# BMS_AFE_-_Communications.net
KiCad netlist of a schematic drawn in Altium Designer
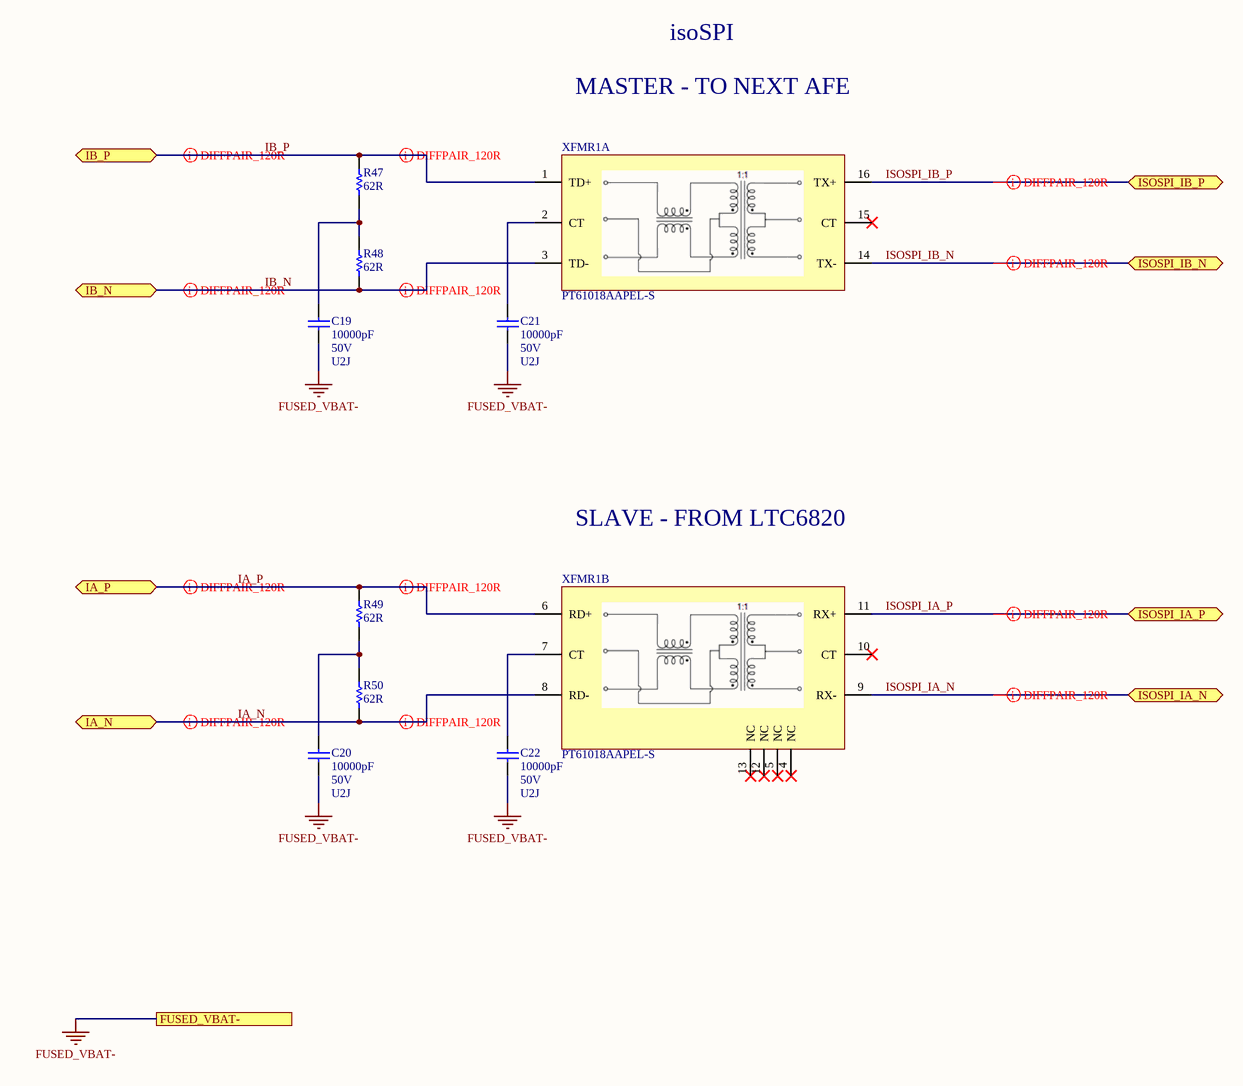
[diagram p0: BMS AFE - Communications.SchDoc]

(export (version "E")
  (design (tool "Eeschema 10.0.6"))
  (components
    (comp (ref "C19")
      (value "CAP CER 10nF 50V 5% X7R 0603")
      (footprint "CAP, 0603")
      (description "10000pF ±5% 50V Ceramic Capacitor U2J 0603 (1608 Metric)")
      (fields
        (field (name "TOLERANCE") "±5%")
        (field (name "CAPACITANCE") "10000pF")
        (field (name "VOLTAGE") "50V")
        (field (name "TEMPERATURE COEFFICIENT") "U2J")
      )
      (libsource (lib "Schematic Diagrams") (part "CAP CER 10nF 50V 5% X7R 0603"))
    )
    (comp (ref "C20")
      (value "CAP CER 10nF 50V 5% X7R 0603")
      (footprint "CAP, 0603")
      (description "10000pF ±5% 50V Ceramic Capacitor U2J 0603 (1608 Metric)")
      (fields
        (field (name "TOLERANCE") "±5%")
        (field (name "CAPACITANCE") "10000pF")
        (field (name "VOLTAGE") "50V")
        (field (name "TEMPERATURE COEFFICIENT") "U2J")
      )
      (libsource (lib "Schematic Diagrams") (part "CAP CER 10nF 50V 5% X7R 0603"))
    )
    (comp (ref "C21")
      (value "CAP CER 10nF 50V 5% X7R 0603")
      (footprint "CAP, 0603")
      (description "10000pF ±5% 50V Ceramic Capacitor U2J 0603 (1608 Metric)")
      (fields
        (field (name "TOLERANCE") "±5%")
        (field (name "CAPACITANCE") "10000pF")
        (field (name "VOLTAGE") "50V")
        (field (name "TEMPERATURE COEFFICIENT") "U2J")
      )
      (libsource (lib "Schematic Diagrams") (part "CAP CER 10nF 50V 5% X7R 0603"))
    )
    (comp (ref "C22")
      (value "CAP CER 10nF 50V 5% X7R 0603")
      (footprint "CAP, 0603")
      (description "10000pF ±5% 50V Ceramic Capacitor U2J 0603 (1608 Metric)")
      (fields
        (field (name "TOLERANCE") "±5%")
        (field (name "CAPACITANCE") "10000pF")
        (field (name "VOLTAGE") "50V")
        (field (name "TEMPERATURE COEFFICIENT") "U2J")
      )
      (libsource (lib "Schematic Diagrams") (part "CAP CER 10nF 50V 5% X7R 0603"))
    )
    (comp (ref "R47")
      (value "62R")
      (footprint "RES, 0603")
      (description "62 Ohms ±0.1% 0.1W, 1/10W Chip Resistor 0603 (1608 Metric) Automotive AEC-Q200 Thin Film")
      (fields
        (field (name "MANUFACTURER") "Panasonic Electronic Components")
        (field (name "MANUFACTURER PART NUMBER") "ERA-3AEB620V")
      )
      (libsource (lib "Schematic Diagrams") (part "RES 62 OHM 0.1% 1/10W 0603"))
    )
    (comp (ref "R48")
      (value "62R")
      (footprint "RES, 0603")
      (description "62 Ohms ±0.1% 0.1W, 1/10W Chip Resistor 0603 (1608 Metric) Automotive AEC-Q200 Thin Film")
      (fields
        (field (name "MANUFACTURER") "Panasonic Electronic Components")
        (field (name "MANUFACTURER PART NUMBER") "ERA-3AEB620V")
      )
      (libsource (lib "Schematic Diagrams") (part "RES 62 OHM 0.1% 1/10W 0603"))
    )
    (comp (ref "R49")
      (value "62R")
      (footprint "RES, 0603")
      (description "62 Ohms ±0.1% 0.1W, 1/10W Chip Resistor 0603 (1608 Metric) Automotive AEC-Q200 Thin Film")
      (fields
        (field (name "MANUFACTURER") "Panasonic Electronic Components")
        (field (name "MANUFACTURER PART NUMBER") "ERA-3AEB620V")
      )
      (libsource (lib "Schematic Diagrams") (part "RES 62 OHM 0.1% 1/10W 0603"))
    )
    (comp (ref "R50")
      (value "62R")
      (footprint "RES, 0603")
      (description "62 Ohms ±0.1% 0.1W, 1/10W Chip Resistor 0603 (1608 Metric) Automotive AEC-Q200 Thin Film")
      (fields
        (field (name "MANUFACTURER") "Panasonic Electronic Components")
        (field (name "MANUFACTURER PART NUMBER") "ERA-3AEB620V")
      )
      (libsource (lib "Schematic Diagrams") (part "RES 62 OHM 0.1% 1/10W 0603"))
    )
    (comp (ref "XFMR1")
      (value "IC PULSE XFMR 1CT:1CT 350UH SMD")
      (footprint "IC, PULSE XFMR 1CT:1CT 350UH SMD")
      (description "PULSE XFMR 1CT:1CT 350UH SMD")
      (fields (field (name "MANUFACTURER") "Bourns Inc.") (field (name "MFG_PN") "PT61018AAPEL-S"))
      (libsource (lib "Schematic Diagrams") (part "IC PULSE XFMR 1CT{colon}1CT 350UH SMD"))
    )
  )
  (nets
    (net (code "1") (name "/IA_N") (class "Default")
      (node (ref "R50") (pin "2") (pinfunction "2_2") (pintype "passive"))
      (node (ref "XFMR1") (pin "8") (pinfunction "RD-_8") (pintype "passive"))
    )
    (net (code "2") (name "/IA_P") (class "Default")
      (node (ref "R49") (pin "1") (pinfunction "1_1") (pintype "passive"))
      (node (ref "XFMR1") (pin "6") (pinfunction "RD+_6") (pintype "passive"))
    )
    (net (code "3") (name "/IB_N") (class "Default")
      (node (ref "R48") (pin "2") (pinfunction "2_2") (pintype "passive"))
      (node (ref "XFMR1") (pin "3") (pinfunction "TD-_3") (pintype "passive"))
    )
    (net (code "4") (name "/IB_P") (class "Default")
      (node (ref "R47") (pin "1") (pinfunction "1_1") (pintype "passive"))
      (node (ref "XFMR1") (pin "1") (pinfunction "TD+_1") (pintype "passive"))
    )
    (net (code "5") (name "/ISOSPI_IA_N") (class "Default")
      (node (ref "XFMR1") (pin "9") (pinfunction "RX-_9") (pintype "passive"))
    )
    (net (code "6") (name "/ISOSPI_IA_P") (class "Default")
      (node (ref "XFMR1") (pin "11") (pinfunction "RX+_11") (pintype "passive"))
    )
    (net (code "7") (name "/ISOSPI_IB_N") (class "Default")
      (node (ref "XFMR1") (pin "14") (pinfunction "TX-_14") (pintype "passive"))
    )
    (net (code "8") (name "/ISOSPI_IB_P") (class "Default")
      (node (ref "XFMR1") (pin "16") (pinfunction "TX+_16") (pintype "passive"))
    )
    (net (code "9") (name "FUSED_VBAT-") (class "Default")
      (node (ref "C19") (pin "2") (pinfunction "2_2") (pintype "passive"))
      (node (ref "C20") (pin "2") (pinfunction "2_2") (pintype "passive"))
      (node (ref "C21") (pin "2") (pinfunction "2_2") (pintype "passive"))
      (node (ref "C22") (pin "2") (pinfunction "2_2") (pintype "passive"))
    )
    (net (code "10") (name "Net-(C19-Pad1)") (class "Default")
      (node (ref "C19") (pin "1") (pinfunction "1_1") (pintype "passive"))
      (node (ref "R47") (pin "2") (pinfunction "2_2") (pintype "passive"))
      (node (ref "R48") (pin "1") (pinfunction "1_1") (pintype "passive"))
    )
    (net (code "11") (name "Net-(C20-Pad1)") (class "Default")
      (node (ref "C20") (pin "1") (pinfunction "1_1") (pintype "passive"))
      (node (ref "R49") (pin "2") (pinfunction "2_2") (pintype "passive"))
      (node (ref "R50") (pin "1") (pinfunction "1_1") (pintype "passive"))
    )
    (net (code "12") (name "Net-(C21-Pad1)") (class "Default")
      (node (ref "C21") (pin "1") (pinfunction "1_1") (pintype "passive"))
      (node (ref "XFMR1") (pin "2") (pinfunction "CT_2") (pintype "passive"))
    )
    (net (code "13") (name "Net-(C22-Pad1)") (class "Default")
      (node (ref "C22") (pin "1") (pinfunction "1_1") (pintype "passive"))
      (node (ref "XFMR1") (pin "7") (pinfunction "CT_7") (pintype "passive"))
    )
    (net (code "14") (name "unconnected-(XFMR1A-CT-Pad15)") (class "Default")
      (node (ref "XFMR1") (pin "15") (pinfunction "CT_15") (pintype "passive+no_connect"))
    )
    (net (code "15") (name "unconnected-(XFMR1B-CT-Pad10)") (class "Default")
      (node (ref "XFMR1") (pin "10") (pinfunction "CT_10") (pintype "passive+no_connect"))
    )
    (net (code "16") (name "unconnected-(XFMR1B-NC-Pad4)") (class "Default")
      (node (ref "XFMR1") (pin "4") (pinfunction "NC_4") (pintype "passive+no_connect"))
    )
    (net (code "17") (name "unconnected-(XFMR1B-NC-Pad5)") (class "Default")
      (node (ref "XFMR1") (pin "5") (pinfunction "NC_5") (pintype "passive+no_connect"))
    )
    (net (code "18") (name "unconnected-(XFMR1B-NC-Pad12)") (class "Default")
      (node (ref "XFMR1") (pin "12") (pinfunction "NC_12") (pintype "passive+no_connect"))
    )
    (net (code "19") (name "unconnected-(XFMR1B-NC-Pad13)") (class "Default")
      (node (ref "XFMR1") (pin "13") (pinfunction "NC_13") (pintype "passive+no_connect"))
    )
  )
)
